# Power.net
KiCad netlist of a schematic drawn in Altium Designer
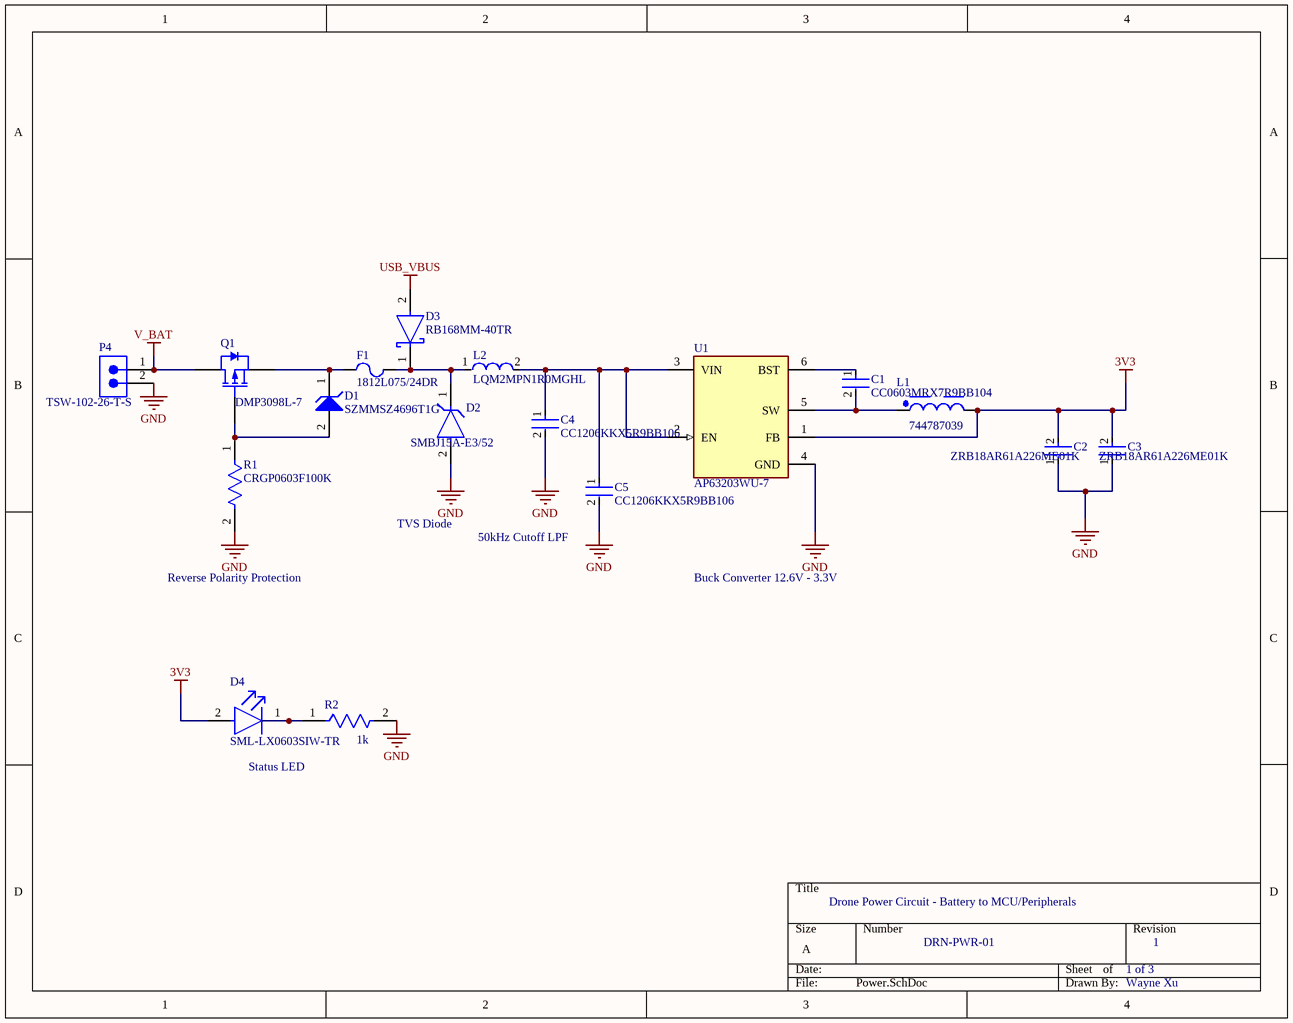
[diagram p0: Power.SchDoc]

(export (version "E")
  (design (tool "Eeschema 10.0.6"))
  (components
    (comp (ref "C1")
      (value "CC0603MRX7R9BB104")
      (footprint "FP-CC0603-DA-MFG")
      (description "CAP CER 0.1UF 50V X7R 0603")
      (fields
        (field (name "MANUFACTURER") "YAGEO")
        (field (name "OCTOPART") "https://octopart.com/cc0603mrx7r9bb104-yageo-67308423")
      )
      (libsource (lib "Altium Content Vault") (part "11868f565c42a9108669ba33697ecf6"))
    )
    (comp (ref "C2")
      (value "ZRB18AR61A226ME01K")
      (footprint "FP-ZRB18A-0_2-MFG")
      (description "CAP CER MLCC")
      (libsource (lib "Altium Content Vault") (part "236180d848d6139a670b325ea6854c9"))
    )
    (comp (ref "C3")
      (value "ZRB18AR61A226ME01K")
      (footprint "FP-ZRB18A-0_2-MFG")
      (description "CAP CER MLCC")
      (libsource (lib "Altium Content Vault") (part "236180d848d6139a670b325ea6854c9"))
    )
    (comp (ref "C4")
      (value "CC1206KKX5R9BB106")
      (footprint "FP-CC1206-FD-MFG")
      (description "CAP CER 10UF 50V X5R 1206")
      (fields (field (name "TOLERANCE") "10%"))
      (libsource (lib "Altium Content Vault") (part "b4654b650e69147ec39a6b967a45e02"))
    )
    (comp (ref "C5")
      (value "CC1206KKX5R9BB106")
      (footprint "FP-CC1206-FD-MFG")
      (description "CAP CER 10UF 50V X5R 1206")
      (fields (field (name "TOLERANCE") "10%"))
      (libsource (lib "Altium Content Vault") (part "b4654b650e69147ec39a6b967a45e02"))
    )
    (comp (ref "D1")
      (value "SZMMSZ4696T1G")
      (footprint "ONSC-SOD-123-2-425-04_V")
      (description "Zener Voltage Regulator, 500 mW, 2-Pin SOD-123, Pb-Free, Tape and Reel")
      (fields (field (name "MANUFACTURER") "On Semiconductor"))
      (libsource (lib "Altium Content Vault") (part "ONSC-K1A2-2"))
    )
    (comp (ref "D2")
      (value "SMBJ15A-E3/52")
      (footprint "FP-95401-MFG")
      (description "TVS DIODE 15V 24.4V DO214AA")
      (fields
        (field (name "MANUFACTURER") "Vishay")
        (field (name "OCTOPART") "https://octopart.com/smbj15a-e3%2F52-vishay-39558613")
      )
      (libsource (lib "Altium Content Vault") (part "f813f71cba58e380607f5dd3caf9714"))
    )
    (comp (ref "D3")
      (value "RB168MM-40TR")
      (footprint "FP-PMDU-MFG")
      (description "DIODE SCHOTTKY 40V 1A PMDU")
      (fields
        (field (name "MANUFACTURER") "Rohm")
        (field (name "OCTOPART") "https://octopart.com/rb168mm-40tr-rohm-65063949")
      )
      (libsource (lib "Altium Content Vault") (part "c1678fac7984e62e0809fbf79c06691"))
    )
    (comp (ref "D4")
      (value "SML-LX0603SIW-TR")
      (footprint "FP-SML-LX0603SIW-TR-MFG")
      (description "LED RED DIFFUSED SMD")
      (libsource (lib "Altium Content Vault") (part "8706943c75ba83719d021d2fdc84c58"))
    )
    (comp (ref "F1")
      (value "1812L075/24DR")
      (footprint "LFUS-1812L07524DR_V")
      (description "Poly-Fuse(R) Resettable PTC, 24 V, 100 A, -40 to 85 degC, 2-Pin SMD, RoHS, Tape and Reel")
      (fields (field (name "MANUFACTURER") "Littelfuse"))
      (libsource (lib "Altium Content Vault") (part "FUSE-2"))
    )
    (comp (ref "L1")
      (value "744787039")
      (footprint "WE-PD2SR_7850")
      (description "Fixed Ind 3.9UH 3.8A 20 Mohm SMD")
      (fields (field (name "TOLERANCE") "30%"))
      (libsource (lib "Altium Content Vault") (part "Inductor - 2"))
    )
    (comp (ref "L2")
      (value "LQM2MPN1R0MGHL")
      (footprint "FP-LQM2MPN_GH-MFG")
      (description "FIXED IND 1UH 1.9A 80 MOHM SMD")
      (fields (field (name "TOLERANCE") "20%"))
      (libsource (lib "Altium Content Vault") (part "502f83bc23984430b7dc9f27bdcf63f"))
    )
    (comp (ref "P4")
      (value "TSW-102-26-T-S")
      (footprint "SMTC-TSW-102-26-XX-S")
      (description "0.025\" SQ Post Header, Through-hole, Vertical, -55 to 105 degC, 2.54 mm Pitch, 2-Pin, Male, RoHS")
      (fields (field (name "MANUFACTURER") "Samtec"))
      (libsource (lib "Altium Content Vault") (part "SMTC-TSW-102-X-X-S-X"))
    )
    (comp (ref "Q1")
      (value "DMP3098L-7")
      (footprint "DIOD-SOT23-3_V")
      (description "P-Channel Enhancement Mode MOSFET, -30 V VDS, -55 to 155 degC, 3-Pin SOT23, RoHS, Tape and Reel")
      (fields (field (name "MANUFACTURER") "Diodes Inc"))
      (libsource (lib "Altium Content Vault") (part "DIOD-PEMOS-G1S2D3-3"))
    )
    (comp (ref "R1")
      (value "CRGP0603F100K")
      (footprint "FP-CRGP0603-IPC_C")
      (description "CRGP 0603 100K 1%")
      (fields
        (field (name "MANUFACTURER") "TE")
        (field (name "OCTOPART") "https://octopart.com/crgp0603f100k-te+connectivity-91018719")
      )
      (libsource (lib "Altium Content Vault") (part "1029c3af85768c4190bb7ad29bc67b5"))
    )
    (comp (ref "R2")
      (value "1k")
      (footprint "FP-CRGCQ0402-IPC_C")
      (description "CRGCQ0402 1KΩ 1% ±100ppm/°C 50V")
      (fields (field (name "MANUFACTURER PART NUMBER") "CRGCQ0402F1K0") (field (name "TOLERANCE") "0.01"))
      (libsource (lib "Altium Content Vault") (part "1029c3af85768c4190bb7ad29bc67b5"))
    )
    (comp (ref "U1")
      (value "AP63203WU-7")
      (footprint "FP-TSOT26-MFG")
      (description "IC REG BUCK 3.3V 2A TSOT26")
      (fields
        (field (name "MANUFACTURER") "Diodes Inc.")
        (field (name "OCTOPART") "https://octopart.com/ap63203wu-7-diodes+inc.-98099550")
      )
      (libsource (lib "Altium Content Vault") (part "0e61c2974d7114b43f01ef96ae2e524"))
    )
  )
  (nets
    (net (code "1") (name "3V3") (class "Default")
      (node (ref "C2") (pin "2") (pinfunction "2_2") (pintype "passive"))
      (node (ref "C3") (pin "2") (pinfunction "2_2") (pintype "passive"))
      (node (ref "D4") (pin "2") (pinfunction "A_2") (pintype "passive"))
      (node (ref "L1") (pin "2") (pinfunction "2_2") (pintype "passive"))
      (node (ref "U1") (pin "1") (pinfunction "FB_1") (pintype "passive"))
    )
    (net (code "2") (name "GND") (class "Default")
      (node (ref "C2") (pin "1") (pinfunction "1_1") (pintype "passive"))
      (node (ref "C3") (pin "1") (pinfunction "1_1") (pintype "passive"))
      (node (ref "C4") (pin "2") (pinfunction "2_2") (pintype "passive"))
      (node (ref "C5") (pin "2") (pinfunction "2_2") (pintype "passive"))
      (node (ref "D2") (pin "2") (pinfunction "A_2") (pintype "passive"))
      (node (ref "P4") (pin "2") (pinfunction "2_2") (pintype "passive"))
      (node (ref "R1") (pin "2") (pinfunction "2_2") (pintype "passive"))
      (node (ref "R2") (pin "2") (pinfunction "2_2") (pintype "passive"))
      (node (ref "U1") (pin "4") (pinfunction "GND_4") (pintype "power_in"))
    )
    (net (code "3") (name "Net-(D1-A)") (class "Default")
      (node (ref "D1") (pin "2") (pinfunction "A_2") (pintype "passive"))
      (node (ref "Q1") (pin "1") (pinfunction "G_1") (pintype "passive"))
      (node (ref "R1") (pin "1") (pinfunction "1_1") (pintype "passive"))
    )
    (net (code "4") (name "Net-(D1-K)") (class "Default")
      (node (ref "D1") (pin "1") (pinfunction "K_1") (pintype "passive"))
      (node (ref "F1") (pin "1") (pinfunction "1_1") (pintype "passive"))
      (node (ref "Q1") (pin "2") (pinfunction "S_2") (pintype "passive"))
    )
    (net (code "5") (name "Net-(D2-C)") (class "Default")
      (node (ref "D2") (pin "1") (pinfunction "C_1") (pintype "passive"))
      (node (ref "D3") (pin "1") (pinfunction "C_1") (pintype "passive"))
      (node (ref "F1") (pin "2") (pinfunction "2_2") (pintype "passive"))
      (node (ref "L2") (pin "1") (pinfunction "1_1") (pintype "passive"))
    )
    (net (code "6") (name "Net-(D4-C)") (class "Default")
      (node (ref "D4") (pin "1") (pinfunction "C_1") (pintype "passive"))
      (node (ref "R2") (pin "1") (pinfunction "1_1") (pintype "passive"))
    )
    (net (code "7") (name "Net-(U1-BST)") (class "Default")
      (node (ref "C1") (pin "1") (pinfunction "1_1") (pintype "passive"))
      (node (ref "U1") (pin "6") (pinfunction "BST_6") (pintype "passive"))
    )
    (net (code "8") (name "Net-(U1-EN)") (class "Default")
      (node (ref "C4") (pin "1") (pinfunction "1_1") (pintype "passive"))
      (node (ref "C5") (pin "1") (pinfunction "1_1") (pintype "passive"))
      (node (ref "L2") (pin "2") (pinfunction "2_2") (pintype "passive"))
      (node (ref "U1") (pin "2") (pinfunction "EN_2") (pintype "input"))
      (node (ref "U1") (pin "3") (pinfunction "VIN_3") (pintype "power_in"))
    )
    (net (code "9") (name "Net-(U1-SW)") (class "Default")
      (node (ref "C1") (pin "2") (pinfunction "2_2") (pintype "passive"))
      (node (ref "L1") (pin "1") (pinfunction "1_1") (pintype "passive"))
      (node (ref "U1") (pin "5") (pinfunction "SW_5") (pintype "passive"))
    )
    (net (code "10") (name "USB_VBUS") (class "Default")
      (node (ref "D3") (pin "2") (pinfunction "A_2") (pintype "passive"))
    )
    (net (code "11") (name "V_BAT") (class "Default")
      (node (ref "P4") (pin "1") (pinfunction "1_1") (pintype "passive"))
      (node (ref "Q1") (pin "3") (pinfunction "D_3") (pintype "passive"))
    )
  )
)
